# GPSClock.net
KiCad netlist of a schematic drawn in EAGLE
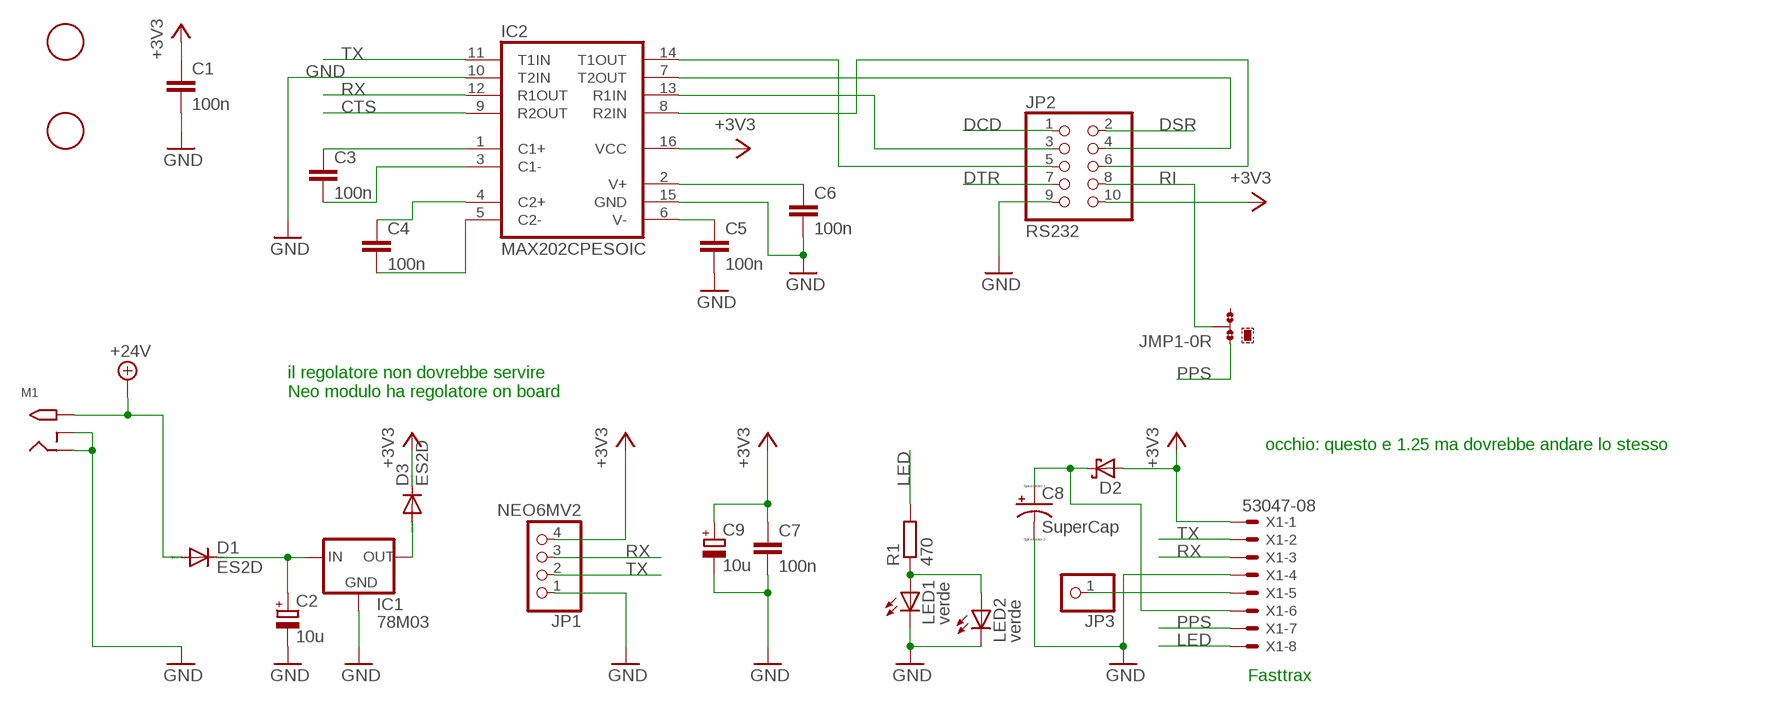
[diagram p0: schematic, sheet 1]

(export (version "E")
  (design (tool "Eeschema 10.0.6"))
  (components
    (comp (ref "C1")
      (value "100n")
      (footprint "eagle-import:C0805")
      (libsource (lib "eagle-import") (part "C-EUC0805"))
    )
    (comp (ref "C2")
      (value "10u")
      (footprint "eagle-import:SMC_D")
      (libsource (lib "eagle-import") (part "CPOL-EUSMCD"))
    )
    (comp (ref "C3")
      (value "100n")
      (footprint "eagle-import:C0805")
      (libsource (lib "eagle-import") (part "C-EUC0805"))
    )
    (comp (ref "C4")
      (value "100n")
      (footprint "eagle-import:C0805")
      (libsource (lib "eagle-import") (part "C-EUC0805"))
    )
    (comp (ref "C5")
      (value "100n")
      (footprint "eagle-import:C0805")
      (libsource (lib "eagle-import") (part "C-EUC0805"))
    )
    (comp (ref "C6")
      (value "100n")
      (footprint "eagle-import:C0805")
      (libsource (lib "eagle-import") (part "C-EUC0805"))
    )
    (comp (ref "C7")
      (value "100n")
      (footprint "eagle-import:C0805")
      (libsource (lib "eagle-import") (part "C-EUC0805"))
    )
    (comp (ref "C8")
      (value "SuperCap")
      (footprint "eagle-import:EB22,5D")
      (libsource (lib "eagle-import") (part "CPOL-USE10-22.5"))
    )
    (comp (ref "C9")
      (value "10u")
      (footprint "eagle-import:SMC_C")
      (libsource (lib "eagle-import") (part "CPOL-EUSMCC"))
    )
    (comp (ref "D1")
      (value "ES2D")
      (footprint "eagle-import:SMB")
      (libsource (lib "eagle-import") (part "ES2D"))
    )
    (comp (ref "D2")
      (value "SCHOTTKY-DIODESMC")
      (footprint "eagle-import:SMC")
      (libsource (lib "eagle-import") (part "SCHOTTKY-DIODESMC"))
    )
    (comp (ref "D3")
      (value "ES2D")
      (footprint "eagle-import:SMB")
      (libsource (lib "eagle-import") (part "ES2D"))
    )
    (comp (ref "F2")
      (value "FIDUCIAL")
      (footprint "eagle-import:FIDUCIAL_1MM")
      (libsource (lib "eagle-import") (part "FIDUCIAL"))
    )
    (comp (ref "F3")
      (value "FIDUCIAL")
      (footprint "eagle-import:FIDUCIAL_1MM")
      (libsource (lib "eagle-import") (part "FIDUCIAL"))
    )
    (comp (ref "IC1")
      (value "78M03")
      (footprint "eagle-import:DPACK")
      (libsource (lib "eagle-import") (part "78MXXSDPACK"))
    )
    (comp (ref "IC2")
      (value "MAX202CPESOIC")
      (footprint "eagle-import:SO16")
      (libsource (lib "eagle-import") (part "MAX202CPESOIC"))
    )
    (comp (ref "JMP1")
      (value "0R-JUMPC")
      (footprint "eagle-import:C0R-JMP")
      (libsource (lib "eagle-import") (part "0R-JUMPC"))
    )
    (comp (ref "JP1")
      (value "NEO6MV2")
      (footprint "eagle-import:1X04")
      (libsource (lib "eagle-import") (part "PINHD-1X4"))
    )
    (comp (ref "JP2")
      (value "RS232")
      (footprint "eagle-import:2X05")
      (libsource (lib "eagle-import") (part "PINHD-2X05_2.54"))
    )
    (comp (ref "JP3")
      (value "PINHD-1X1")
      (footprint "eagle-import:1X01")
      (libsource (lib "eagle-import") (part "PINHD-1X1"))
    )
    (comp (ref "LED1")
      (value "verde")
      (footprint "eagle-import:CHIPLED_0805")
      (libsource (lib "eagle-import") (part "led_LEDCHIPLED_0805"))
    )
    (comp (ref "LED2")
      (value "verde")
      (footprint "eagle-import:LED3MM")
      (libsource (lib "eagle-import") (part "LED3MM"))
    )
    (comp (ref "M1")
      (value "2.1MMJACKTHM")
      (footprint "eagle-import:PJ-102A")
      (libsource (lib "eagle-import") (part "2.1MMJACKTHM"))
    )
    (comp (ref "R1")
      (value "470")
      (footprint "eagle-import:R0805")
      (libsource (lib "eagle-import") (part "R-EU_R0805"))
    )
    (comp (ref "X1")
      (value "53047-08")
      (footprint "eagle-import:53047-08")
      (fields (field (name "MPN") "53047-0810"))
      (libsource (lib "eagle-import") (part "53?-08047"))
    )
  )
  (nets
    (net (code "1") (name "+3V3") (class "Default")
      (node (ref "C1") (pin "1") (pinfunction "1_1") (pintype "passive"))
      (node (ref "C7") (pin "1") (pinfunction "1_1") (pintype "passive"))
      (node (ref "C9") (pin "+") (pinfunction "+_+") (pintype "passive"))
      (node (ref "D2") (pin "A") (pinfunction "A_A") (pintype "passive"))
      (node (ref "D3") (pin "C") (pinfunction "C_C") (pintype "passive"))
      (node (ref "IC2") (pin "16") (pinfunction "VCC_16") (pintype "power_in"))
      (node (ref "JP1") (pin "4") (pinfunction "4_4") (pintype "passive"))
      (node (ref "JP2") (pin "10") (pinfunction "10_10") (pintype "passive"))
      (node (ref "X1") (pin "1") (pinfunction "S_1") (pintype "passive"))
    )
    (net (code "2") (name "+24V") (class "Default")
      (node (ref "D1") (pin "A") (pinfunction "A_A") (pintype "passive"))
      (node (ref "M1") (pin "TIP") (pinfunction "TIP_TIP") (pintype "bidirectional"))
    )
    (net (code "3") (name "/CTS") (class "Default")
      (node (ref "IC2") (pin "9") (pinfunction "R2OUT_9") (pintype "output"))
    )
    (net (code "4") (name "/DCD") (class "Default")
      (node (ref "JP2") (pin "1") (pinfunction "1_1") (pintype "passive"))
    )
    (net (code "5") (name "/DSR") (class "Default")
      (node (ref "JP2") (pin "2") (pinfunction "2_2") (pintype "passive"))
    )
    (net (code "6") (name "/DTR") (class "Default")
      (node (ref "JP2") (pin "7") (pinfunction "7_7") (pintype "passive"))
    )
    (net (code "7") (name "/LED") (class "Default")
      (node (ref "R1") (pin "2") (pinfunction "2_2") (pintype "passive"))
      (node (ref "X1") (pin "8") (pinfunction "S_8") (pintype "passive"))
    )
    (net (code "8") (name "/PPS") (class "Default")
      (node (ref "JMP1") (pin "1") (pinfunction "1_1") (pintype "passive"))
      (node (ref "X1") (pin "7") (pinfunction "S_7") (pintype "passive"))
    )
    (net (code "9") (name "/RI") (class "Default")
      (node (ref "JMP1") (pin "2") (pinfunction "2_2") (pintype "passive"))
      (node (ref "JP2") (pin "8") (pinfunction "8_8") (pintype "passive"))
    )
    (net (code "10") (name "/RX") (class "Default")
      (node (ref "IC2") (pin "12") (pinfunction "R1OUT_12") (pintype "output"))
      (node (ref "JP1") (pin "3") (pinfunction "3_3") (pintype "passive"))
      (node (ref "X1") (pin "3") (pinfunction "S_3") (pintype "passive"))
    )
    (net (code "11") (name "/TX") (class "Default")
      (node (ref "IC2") (pin "11") (pinfunction "T1IN_11") (pintype "input"))
      (node (ref "JP1") (pin "2") (pinfunction "2_2") (pintype "passive"))
      (node (ref "X1") (pin "2") (pinfunction "S_2") (pintype "passive"))
    )
    (net (code "12") (name "GND") (class "Default")
      (node (ref "C1") (pin "2") (pinfunction "2_2") (pintype "passive"))
      (node (ref "C2") (pin "-") (pinfunction "-_-") (pintype "passive"))
      (node (ref "C5") (pin "2") (pinfunction "2_2") (pintype "passive"))
      (node (ref "C6") (pin "2") (pinfunction "2_2") (pintype "passive"))
      (node (ref "C7") (pin "2") (pinfunction "2_2") (pintype "passive"))
      (node (ref "C8") (pin "-") (pinfunction "-_-") (pintype "passive"))
      (node (ref "C9") (pin "-") (pinfunction "-_-") (pintype "passive"))
      (node (ref "IC1") (pin "4") (pinfunction "GND_4") (pintype "input"))
      (node (ref "IC2") (pin "10") (pinfunction "T2IN_10") (pintype "input"))
      (node (ref "IC2") (pin "15") (pinfunction "GND_15") (pintype "power_in"))
      (node (ref "JP1") (pin "1") (pinfunction "1_1") (pintype "passive"))
      (node (ref "JP2") (pin "9") (pinfunction "9_9") (pintype "passive"))
      (node (ref "LED1") (pin "C") (pinfunction "C_C") (pintype "passive"))
      (node (ref "LED2") (pin "K") (pinfunction "C_K") (pintype "passive"))
      (node (ref "M1") (pin "RING") (pinfunction "RING_RING") (pintype "bidirectional"))
      (node (ref "M1") (pin "RING_SW") (pinfunction "RING_SW_RING_SW") (pintype "bidirectional"))
      (node (ref "X1") (pin "4") (pinfunction "S_4") (pintype "passive"))
    )
    (net (code "13") (name "Net-(IC1-IN)") (class "Default")
      (node (ref "C2") (pin "+") (pinfunction "+_+") (pintype "passive"))
      (node (ref "D1") (pin "C") (pinfunction "C_C") (pintype "passive"))
      (node (ref "IC1") (pin "1") (pinfunction "IN_1") (pintype "input"))
    )
    (net (code "14") (name "Net-(IC1-OUT)") (class "Default")
      (node (ref "D3") (pin "A") (pinfunction "A_A") (pintype "passive"))
      (node (ref "IC1") (pin "3") (pinfunction "OUT_3") (pintype "passive"))
    )
    (net (code "15") (name "Net-(IC2-C1+)") (class "Default")
      (node (ref "C3") (pin "1") (pinfunction "1_1") (pintype "passive"))
      (node (ref "IC2") (pin "1") (pinfunction "C1+_1") (pintype "passive"))
    )
    (net (code "16") (name "Net-(IC2-C1-)") (class "Default")
      (node (ref "C3") (pin "2") (pinfunction "2_2") (pintype "passive"))
      (node (ref "IC2") (pin "3") (pinfunction "C1-_3") (pintype "passive"))
    )
    (net (code "17") (name "Net-(IC2-C2+)") (class "Default")
      (node (ref "C4") (pin "1") (pinfunction "1_1") (pintype "passive"))
      (node (ref "IC2") (pin "4") (pinfunction "C2+_4") (pintype "passive"))
    )
    (net (code "18") (name "Net-(IC2-C2-)") (class "Default")
      (node (ref "C4") (pin "2") (pinfunction "2_2") (pintype "passive"))
      (node (ref "IC2") (pin "5") (pinfunction "C2-_5") (pintype "passive"))
    )
    (net (code "19") (name "Net-(IC2-R1IN)") (class "Default")
      (node (ref "IC2") (pin "13") (pinfunction "R1IN_13") (pintype "input"))
      (node (ref "JP2") (pin "3") (pinfunction "3_3") (pintype "passive"))
    )
    (net (code "20") (name "Net-(IC2-R2IN)") (class "Default")
      (node (ref "IC2") (pin "8") (pinfunction "R2IN_8") (pintype "input"))
      (node (ref "JP2") (pin "6") (pinfunction "6_6") (pintype "passive"))
    )
    (net (code "21") (name "Net-(IC2-T1OUT)") (class "Default")
      (node (ref "IC2") (pin "14") (pinfunction "T1OUT_14") (pintype "output"))
      (node (ref "JP2") (pin "5") (pinfunction "5_5") (pintype "passive"))
    )
    (net (code "22") (name "Net-(IC2-T2OUT)") (class "Default")
      (node (ref "IC2") (pin "7") (pinfunction "T2OUT_7") (pintype "output"))
      (node (ref "JP2") (pin "4") (pinfunction "4_4") (pintype "passive"))
    )
    (net (code "23") (name "Net-(IC2-V+)") (class "Default")
      (node (ref "C6") (pin "1") (pinfunction "1_1") (pintype "passive"))
      (node (ref "IC2") (pin "2") (pinfunction "V+_2") (pintype "power_in"))
    )
    (net (code "24") (name "Net-(IC2-V-)") (class "Default")
      (node (ref "C5") (pin "1") (pinfunction "1_1") (pintype "passive"))
      (node (ref "IC2") (pin "6") (pinfunction "V-_6") (pintype "power_in"))
    )
    (net (code "25") (name "Net-(LED1-PadA)") (class "Default")
      (node (ref "LED1") (pin "A") (pinfunction "A_A") (pintype "passive"))
      (node (ref "LED2") (pin "A") (pinfunction "A_A") (pintype "passive"))
      (node (ref "R1") (pin "1") (pinfunction "1_1") (pintype "passive"))
    )
    (net (code "26") (name "Net-(X1E-S)") (class "Default")
      (node (ref "JP3") (pin "1") (pinfunction "1_1") (pintype "passive"))
      (node (ref "X1") (pin "5") (pinfunction "S_5") (pintype "passive"))
    )
    (net (code "27") (name "Net-(X1F-S)") (class "Default")
      (node (ref "C8") (pin "+") (pinfunction "+_+") (pintype "passive"))
      (node (ref "D2") (pin "C") (pinfunction "C_C") (pintype "passive"))
      (node (ref "X1") (pin "6") (pinfunction "S_6") (pintype "passive"))
    )
    (net (code "28") (name "unconnected-(JMP1-Pad3)") (class "Default")
      (node (ref "JMP1") (pin "3") (pinfunction "3_3") (pintype "passive"))
    )
  )
)
